# BQ51050B.net
KiCad netlist of a schematic drawn in EAGLE
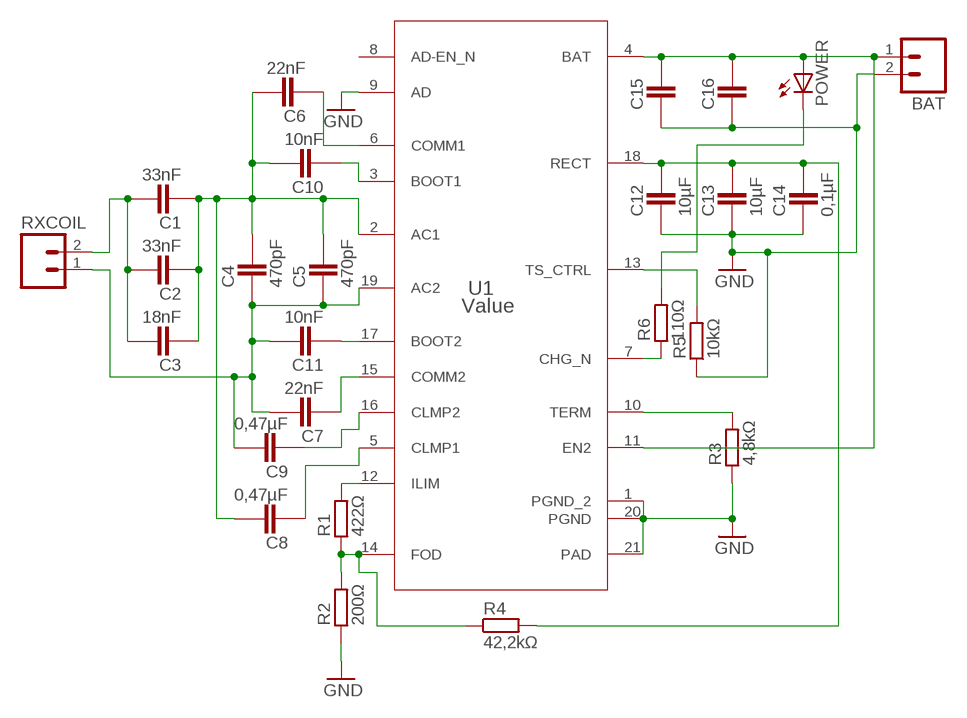
[diagram p0: schematic, sheet 1]

(export (version "E")
  (design (tool "Eeschema 10.0.6"))
  (components
    (comp (ref "BAT")
      (value "M02LOCK")
      (footprint "eagle-import:1X02_LOCK")
      (libsource (lib "eagle-import") (part "M02LOCK"))
    )
    (comp (ref "C1")
      (value "33nF")
      (footprint "eagle-import:CAPC1005X60N")
      (libsource (lib "eagle-import") (part "CAPACITOR_0402"))
    )
    (comp (ref "C2")
      (value "33nF")
      (footprint "eagle-import:CAPC1005X60N")
      (libsource (lib "eagle-import") (part "CAPACITOR_0402"))
    )
    (comp (ref "C3")
      (value "18nF")
      (footprint "eagle-import:CAPC1005X60N")
      (libsource (lib "eagle-import") (part "CAPACITOR_0402"))
    )
    (comp (ref "C4")
      (value "470pF")
      (footprint "eagle-import:CAPC1005X60N")
      (libsource (lib "eagle-import") (part "CAPACITOR_0402"))
    )
    (comp (ref "C5")
      (value "470pF")
      (footprint "eagle-import:CAPC1005X60N")
      (libsource (lib "eagle-import") (part "CAPACITOR_0402"))
    )
    (comp (ref "C6")
      (value "22nF")
      (footprint "eagle-import:CAPC1005X60N")
      (libsource (lib "eagle-import") (part "CAPACITOR_0402"))
    )
    (comp (ref "C7")
      (value "22nF")
      (footprint "eagle-import:CAPC1005X60N")
      (libsource (lib "eagle-import") (part "CAPACITOR_0402"))
    )
    (comp (ref "C8")
      (value "0,47µF")
      (footprint "eagle-import:CAPC1005X60N")
      (libsource (lib "eagle-import") (part "CAPACITOR_0402"))
    )
    (comp (ref "C9")
      (value "0,47µF")
      (footprint "eagle-import:CAPC1005X60N")
      (libsource (lib "eagle-import") (part "CAPACITOR_0402"))
    )
    (comp (ref "C10")
      (value "10nF")
      (footprint "eagle-import:CAPC1005X60N")
      (libsource (lib "eagle-import") (part "CAPACITOR_0402"))
    )
    (comp (ref "C11")
      (value "10nF")
      (footprint "eagle-import:CAPC1005X60N")
      (libsource (lib "eagle-import") (part "CAPACITOR_0402"))
    )
    (comp (ref "C12")
      (value "10µF")
      (footprint "eagle-import:CAPC1608X92N")
      (libsource (lib "eagle-import") (part "CAPACITOR_0603"))
    )
    (comp (ref "C13")
      (value "10µF")
      (footprint "eagle-import:CAPC1608X92N")
      (libsource (lib "eagle-import") (part "CAPACITOR_0603"))
    )
    (comp (ref "C14")
      (value "0,1µF")
      (footprint "eagle-import:CAPC1005X60N")
      (libsource (lib "eagle-import") (part "CAPACITOR_0402"))
    )
    (comp (ref "C15")
      (value "CAPACITOR_0402")
      (footprint "eagle-import:CAPC1005X60N")
      (libsource (lib "eagle-import") (part "CAPACITOR_0402"))
    )
    (comp (ref "C16")
      (value "CAPACITOR_0402")
      (footprint "eagle-import:CAPC1005X60N")
      (libsource (lib "eagle-import") (part "CAPACITOR_0402"))
    )
    (comp (ref "POWER")
      (value "LEDSML0603")
      (footprint "eagle-import:SML0603")
      (libsource (lib "eagle-import") (part "LEDSML0603"))
    )
    (comp (ref "R1")
      (value "422Ω")
      (footprint "eagle-import:RESC1005X40AN")
      (libsource (lib "eagle-import") (part "RESISTOR_0402"))
    )
    (comp (ref "R2")
      (value "200Ω")
      (footprint "eagle-import:RESC1005X40AN")
      (libsource (lib "eagle-import") (part "RESISTOR_0402"))
    )
    (comp (ref "R3")
      (value "4,8kΩ")
      (footprint "eagle-import:RESC1005X40AN")
      (libsource (lib "eagle-import") (part "RESISTOR_0402"))
    )
    (comp (ref "R4")
      (value "42,2kΩ")
      (footprint "eagle-import:RESC1005X40AN")
      (libsource (lib "eagle-import") (part "RESISTOR_0402"))
    )
    (comp (ref "R5")
      (value "10kΩ")
      (footprint "eagle-import:RESC1005X40AN")
      (libsource (lib "eagle-import") (part "RESISTOR_0402"))
    )
    (comp (ref "R6")
      (value "110Ω")
      (footprint "eagle-import:RESC1005X40AN")
      (libsource (lib "eagle-import") (part "RESISTOR_0402"))
    )
    (comp (ref "RXCOIL")
      (value "M02LOCK")
      (footprint "eagle-import:1X02_LOCK")
      (libsource (lib "eagle-import") (part "M02LOCK"))
    )
    (comp (ref "U1")
      (value "Value")
      (footprint "eagle-import:RHL0020A")
      (fields (field (name "MANUFACTURER") "Texas Instruments") (field (name "PARTNUMBER") "BQ51050BRHLR"))
      (libsource (lib "eagle-import") (part "BQ51050BRHLR"))
    )
  )
  (nets
    (net (code "1") (name "GND") (class "Default")
      (node (ref "BAT") (pin "2") (pinfunction "2_2") (pintype "passive"))
      (node (ref "C12") (pin "1") (pinfunction "1_1") (pintype "passive"))
      (node (ref "C13") (pin "1") (pinfunction "1_1") (pintype "passive"))
      (node (ref "C14") (pin "1") (pinfunction "1_1") (pintype "passive"))
      (node (ref "C15") (pin "1") (pinfunction "1_1") (pintype "passive"))
      (node (ref "C16") (pin "1") (pinfunction "1_1") (pintype "passive"))
      (node (ref "R2") (pin "1") (pinfunction "1_1") (pintype "passive"))
      (node (ref "R3") (pin "1") (pinfunction "1_1") (pintype "passive"))
      (node (ref "R5") (pin "1") (pinfunction "1_1") (pintype "passive"))
      (node (ref "U1") (pin "1") (pinfunction "PGND_2_1") (pintype "power_in"))
      (node (ref "U1") (pin "20") (pinfunction "PGND_20") (pintype "power_in"))
      (node (ref "U1") (pin "21") (pinfunction "PAD_21") (pintype "passive"))
      (node (ref "U1") (pin "9") (pinfunction "AD_9") (pintype "input"))
    )
    (net (code "2") (name "Net-(C1-Pad2)") (class "Default")
      (node (ref "C1") (pin "2") (pinfunction "2_2") (pintype "passive"))
      (node (ref "C2") (pin "2") (pinfunction "2_2") (pintype "passive"))
      (node (ref "C3") (pin "2") (pinfunction "2_2") (pintype "passive"))
      (node (ref "RXCOIL") (pin "2") (pinfunction "2_2") (pintype "passive"))
    )
    (net (code "3") (name "Net-(POWER-PadC)") (class "Default")
      (node (ref "POWER") (pin "C") (pinfunction "C_C") (pintype "passive"))
      (node (ref "R6") (pin "2") (pinfunction "2_2") (pintype "passive"))
    )
    (net (code "4") (name "Net-(U1-AC1)") (class "Default")
      (node (ref "C1") (pin "1") (pinfunction "1_1") (pintype "passive"))
      (node (ref "C10") (pin "2") (pinfunction "2_2") (pintype "passive"))
      (node (ref "C2") (pin "1") (pinfunction "1_1") (pintype "passive"))
      (node (ref "C3") (pin "1") (pinfunction "1_1") (pintype "passive"))
      (node (ref "C4") (pin "2") (pinfunction "2_2") (pintype "passive"))
      (node (ref "C5") (pin "2") (pinfunction "2_2") (pintype "passive"))
      (node (ref "C6") (pin "2") (pinfunction "2_2") (pintype "passive"))
      (node (ref "C8") (pin "2") (pinfunction "2_2") (pintype "passive"))
      (node (ref "U1") (pin "2") (pinfunction "AC1_2") (pintype "power_in"))
    )
    (net (code "5") (name "Net-(U1-AC2)") (class "Default")
      (node (ref "C11") (pin "2") (pinfunction "2_2") (pintype "passive"))
      (node (ref "C4") (pin "1") (pinfunction "1_1") (pintype "passive"))
      (node (ref "C5") (pin "1") (pinfunction "1_1") (pintype "passive"))
      (node (ref "C7") (pin "2") (pinfunction "2_2") (pintype "passive"))
      (node (ref "C9") (pin "2") (pinfunction "2_2") (pintype "passive"))
      (node (ref "RXCOIL") (pin "1") (pinfunction "1_1") (pintype "passive"))
      (node (ref "U1") (pin "19") (pinfunction "AC2_19") (pintype "power_in"))
    )
    (net (code "6") (name "Net-(U1-BAT)") (class "Default")
      (node (ref "BAT") (pin "1") (pinfunction "1_1") (pintype "passive"))
      (node (ref "C15") (pin "2") (pinfunction "2_2") (pintype "passive"))
      (node (ref "C16") (pin "2") (pinfunction "2_2") (pintype "passive"))
      (node (ref "POWER") (pin "A") (pinfunction "A_A") (pintype "passive"))
      (node (ref "U1") (pin "11") (pinfunction "EN2_11") (pintype "input"))
      (node (ref "U1") (pin "4") (pinfunction "BAT_4") (pintype "power_in"))
    )
    (net (code "7") (name "Net-(U1-BOOT1)") (class "Default")
      (node (ref "C10") (pin "1") (pinfunction "1_1") (pintype "passive"))
      (node (ref "U1") (pin "3") (pinfunction "BOOT1_3") (pintype "power_in"))
    )
    (net (code "8") (name "Net-(U1-BOOT2)") (class "Default")
      (node (ref "C11") (pin "1") (pinfunction "1_1") (pintype "passive"))
      (node (ref "U1") (pin "17") (pinfunction "BOOT2_17") (pintype "power_in"))
    )
    (net (code "9") (name "Net-(U1-CHG_N)") (class "Default")
      (node (ref "R6") (pin "1") (pinfunction "1_1") (pintype "passive"))
      (node (ref "U1") (pin "7") (pinfunction "CHG_N_7") (pintype "output"))
    )
    (net (code "10") (name "Net-(U1-CLMP1)") (class "Default")
      (node (ref "C8") (pin "1") (pinfunction "1_1") (pintype "passive"))
      (node (ref "U1") (pin "5") (pinfunction "CLMP1_5") (pintype "output"))
    )
    (net (code "11") (name "Net-(U1-CLMP2)") (class "Default")
      (node (ref "C9") (pin "1") (pinfunction "1_1") (pintype "passive"))
      (node (ref "U1") (pin "16") (pinfunction "CLMP2_16") (pintype "output"))
    )
    (net (code "12") (name "Net-(U1-COMM1)") (class "Default")
      (node (ref "C6") (pin "1") (pinfunction "1_1") (pintype "passive"))
      (node (ref "U1") (pin "6") (pinfunction "COMM1_6") (pintype "output"))
    )
    (net (code "13") (name "Net-(U1-COMM2)") (class "Default")
      (node (ref "C7") (pin "1") (pinfunction "1_1") (pintype "passive"))
      (node (ref "U1") (pin "15") (pinfunction "COMM2_15") (pintype "output"))
    )
    (net (code "14") (name "Net-(U1-FOD)") (class "Default")
      (node (ref "R1") (pin "1") (pinfunction "1_1") (pintype "passive"))
      (node (ref "R2") (pin "2") (pinfunction "2_2") (pintype "passive"))
      (node (ref "R4") (pin "1") (pinfunction "1_1") (pintype "passive"))
      (node (ref "U1") (pin "14") (pinfunction "FOD_14") (pintype "input"))
    )
    (net (code "15") (name "Net-(U1-ILIM)") (class "Default")
      (node (ref "R1") (pin "2") (pinfunction "2_2") (pintype "passive"))
      (node (ref "U1") (pin "12") (pinfunction "ILIM_12") (pintype "bidirectional"))
    )
    (net (code "16") (name "Net-(U1-RECT)") (class "Default")
      (node (ref "C12") (pin "2") (pinfunction "2_2") (pintype "passive"))
      (node (ref "C13") (pin "2") (pinfunction "2_2") (pintype "passive"))
      (node (ref "C14") (pin "2") (pinfunction "2_2") (pintype "passive"))
      (node (ref "R4") (pin "2") (pinfunction "2_2") (pintype "passive"))
      (node (ref "U1") (pin "18") (pinfunction "RECT_18") (pintype "power_in"))
    )
    (net (code "17") (name "Net-(U1-TERM)") (class "Default")
      (node (ref "R3") (pin "2") (pinfunction "2_2") (pintype "passive"))
      (node (ref "U1") (pin "10") (pinfunction "TERM_10") (pintype "input"))
    )
    (net (code "18") (name "Net-(U1-TS_CTRL)") (class "Default")
      (node (ref "R5") (pin "2") (pinfunction "2_2") (pintype "passive"))
      (node (ref "U1") (pin "13") (pinfunction "TS_CTRL_13") (pintype "input"))
    )
    (net (code "19") (name "unconnected-(U1-AD-EN_N-Pad8)") (class "Default")
      (node (ref "U1") (pin "8") (pinfunction "AD-EN_N_8") (pintype "output"))
    )
  )
)
